# C64_KernalSw_8k.net
KiCad netlist of a schematic drawn in EAGLE
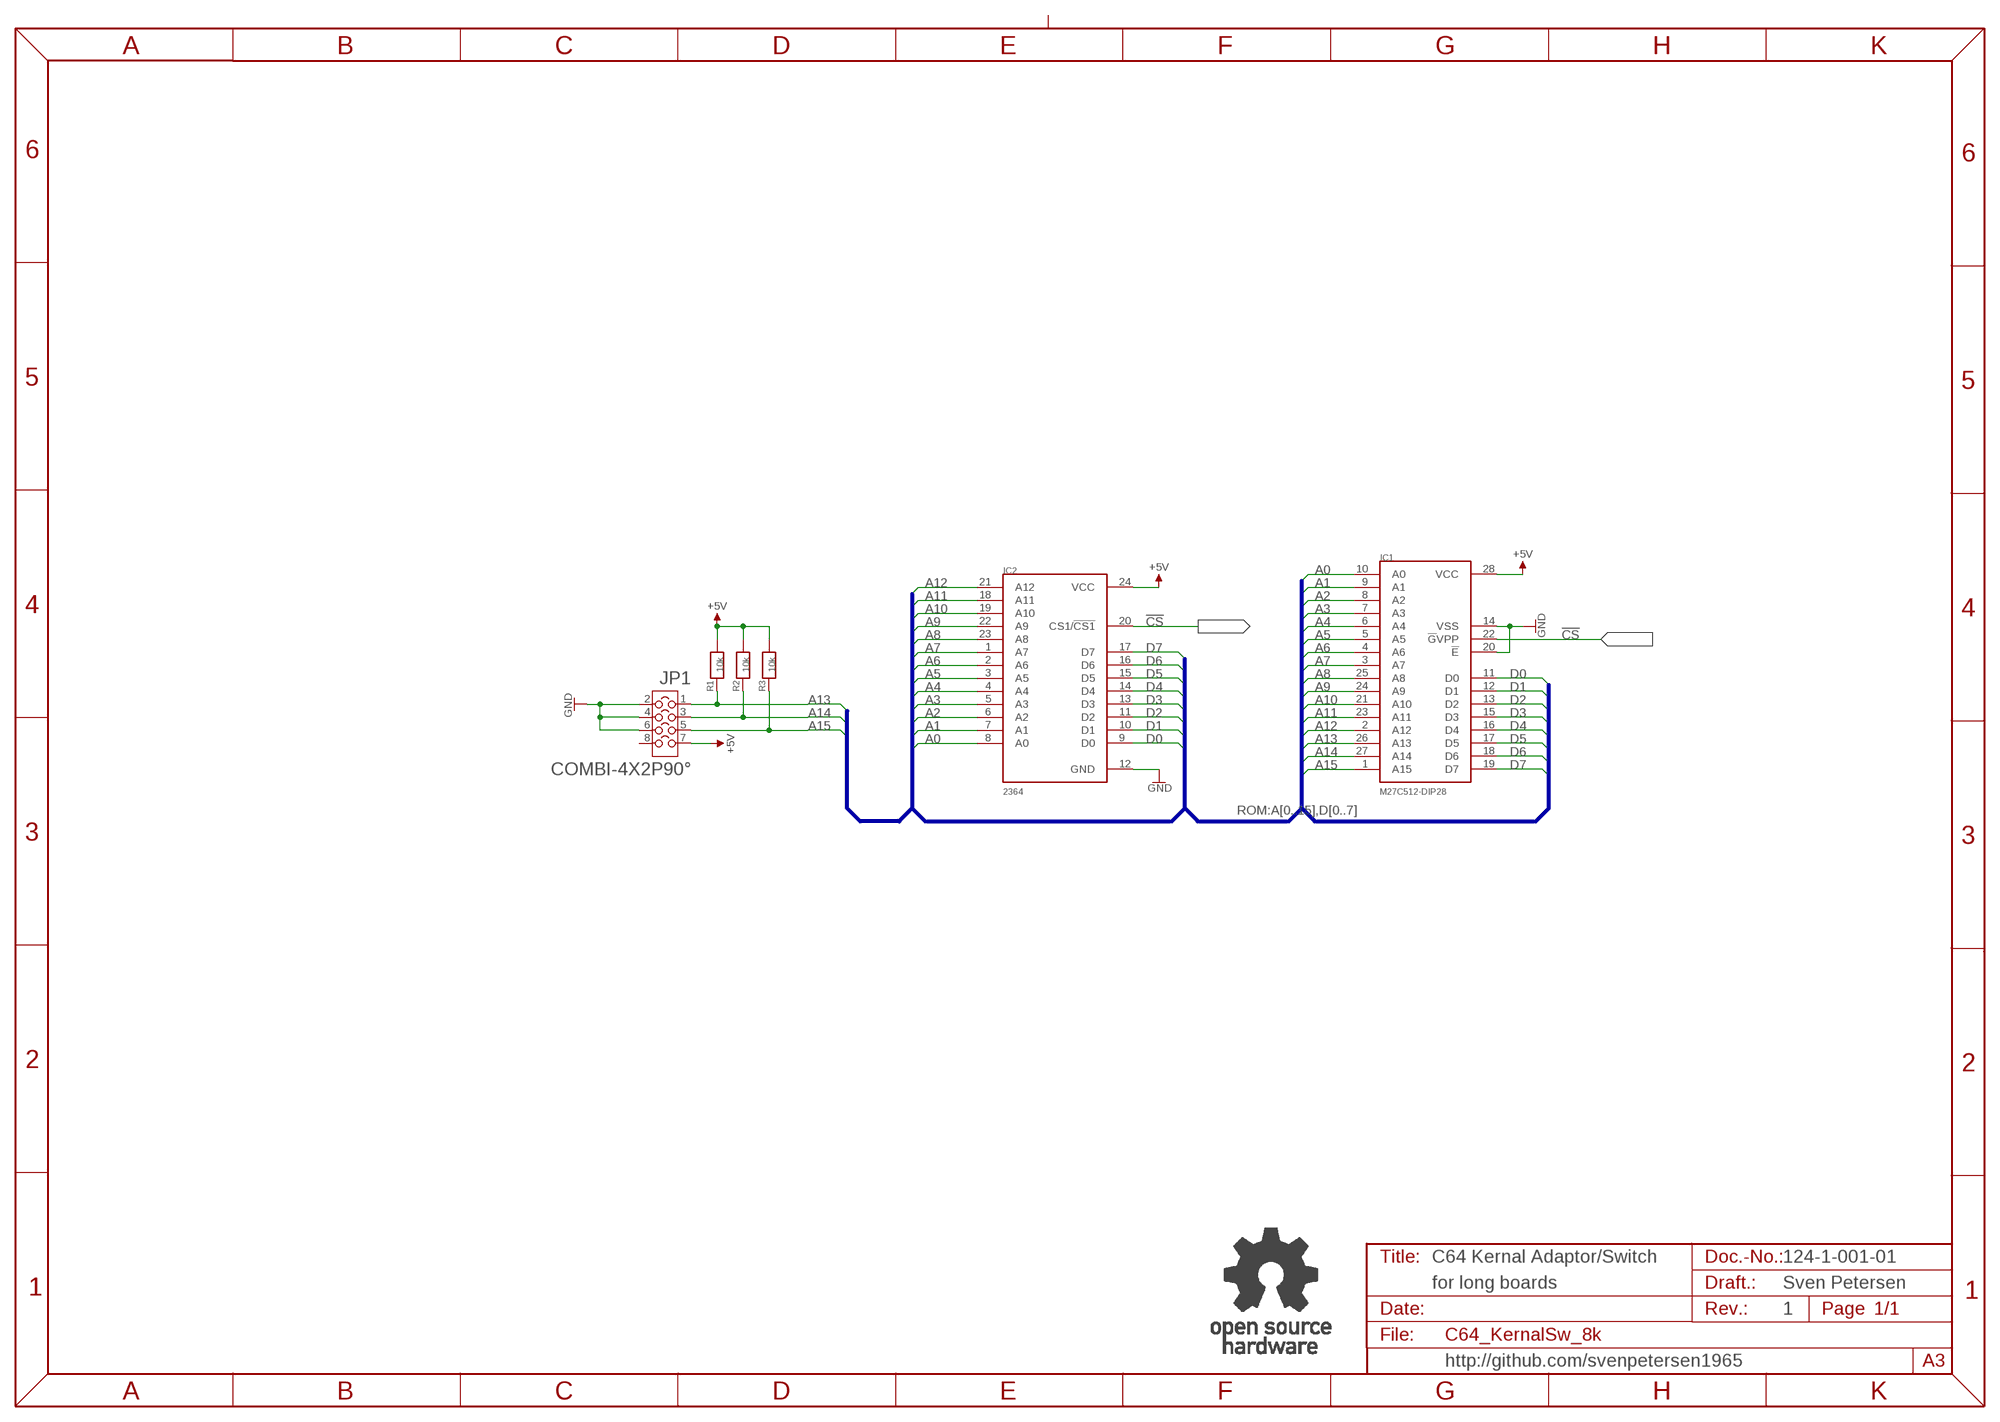
[diagram p0: schematic, sheet 1]

(export (version "E")
  (design (tool "Eeschema 10.0.6"))
  (components
    (comp (ref "IC1")
      (value "M27C512-DIP28")
      (footprint "eagle-import:DIL28-6")
      (libsource (lib "eagle-import") (part "M27C512-DIP28"))
    )
    (comp (ref "IC2")
      (value "2364")
      (footprint "eagle-import:DIL24_SOCKET")
      (libsource (lib "eagle-import") (part "2364"))
    )
    (comp (ref "JP1")
      (value "COMBI-4X2P90°")
      (footprint "eagle-import:COMBI-4X2-90")
      (libsource (lib "eagle-import") (part "COMBI-4X2P90°"))
    )
    (comp (ref "R1")
      (value "10k")
      (footprint "eagle-import:0805")
      (libsource (lib "eagle-import") (part "R-0805"))
    )
    (comp (ref "R2")
      (value "10k")
      (footprint "eagle-import:0805")
      (libsource (lib "eagle-import") (part "R-0805"))
    )
    (comp (ref "R3")
      (value "10k")
      (footprint "eagle-import:0805")
      (libsource (lib "eagle-import") (part "R-0805"))
    )
    (comp (ref "U$11")
      (value "OPEN_SOURCE_HW")
      (footprint "eagle-import:OPENHW")
      (libsource (lib "eagle-import") (part "OPEN_SOURCE_HW"))
    )
  )
  (nets
    (net (code "1") (name "+5V") (class "Default")
      (node (ref "IC1") (pin "28") (pinfunction "VCC_28") (pintype "power_in"))
      (node (ref "IC2") (pin "24") (pinfunction "VCC_24") (pintype "power_in"))
      (node (ref "JP1") (pin "7") (pinfunction "7_7") (pintype "bidirectional"))
      (node (ref "R1") (pin "2") (pinfunction "2_2") (pintype "passive"))
      (node (ref "R2") (pin "2") (pinfunction "2_2") (pintype "passive"))
      (node (ref "R3") (pin "2") (pinfunction "2_2") (pintype "passive"))
    )
    (net (code "2") (name "/A0") (class "Default")
      (node (ref "IC1") (pin "10") (pinfunction "A0_10") (pintype "input"))
      (node (ref "IC2") (pin "8") (pinfunction "A0_8") (pintype "input"))
    )
    (net (code "3") (name "/A1") (class "Default")
      (node (ref "IC1") (pin "9") (pinfunction "A1_9") (pintype "input"))
      (node (ref "IC2") (pin "7") (pinfunction "A1_7") (pintype "input"))
    )
    (net (code "4") (name "/A2") (class "Default")
      (node (ref "IC1") (pin "8") (pinfunction "A2_8") (pintype "input"))
      (node (ref "IC2") (pin "6") (pinfunction "A2_6") (pintype "input"))
    )
    (net (code "5") (name "/A3") (class "Default")
      (node (ref "IC1") (pin "7") (pinfunction "A3_7") (pintype "input"))
      (node (ref "IC2") (pin "5") (pinfunction "A3_5") (pintype "input"))
    )
    (net (code "6") (name "/A4") (class "Default")
      (node (ref "IC1") (pin "6") (pinfunction "A4_6") (pintype "input"))
      (node (ref "IC2") (pin "4") (pinfunction "A4_4") (pintype "input"))
    )
    (net (code "7") (name "/A5") (class "Default")
      (node (ref "IC1") (pin "5") (pinfunction "A5_5") (pintype "input"))
      (node (ref "IC2") (pin "3") (pinfunction "A5_3") (pintype "input"))
    )
    (net (code "8") (name "/A6") (class "Default")
      (node (ref "IC1") (pin "4") (pinfunction "A6_4") (pintype "input"))
      (node (ref "IC2") (pin "2") (pinfunction "A6_2") (pintype "input"))
    )
    (net (code "9") (name "/A7") (class "Default")
      (node (ref "IC1") (pin "3") (pinfunction "A7_3") (pintype "input"))
      (node (ref "IC2") (pin "1") (pinfunction "A7_1") (pintype "input"))
    )
    (net (code "10") (name "/A8") (class "Default")
      (node (ref "IC1") (pin "25") (pinfunction "A8_25") (pintype "input"))
      (node (ref "IC2") (pin "23") (pinfunction "A8_23") (pintype "input"))
    )
    (net (code "11") (name "/A9") (class "Default")
      (node (ref "IC1") (pin "24") (pinfunction "A9_24") (pintype "input"))
      (node (ref "IC2") (pin "22") (pinfunction "A9_22") (pintype "input"))
    )
    (net (code "12") (name "/A10") (class "Default")
      (node (ref "IC1") (pin "21") (pinfunction "A10_21") (pintype "input"))
      (node (ref "IC2") (pin "19") (pinfunction "A10_19") (pintype "input"))
    )
    (net (code "13") (name "/A11") (class "Default")
      (node (ref "IC1") (pin "23") (pinfunction "A11_23") (pintype "input"))
      (node (ref "IC2") (pin "18") (pinfunction "A11_18") (pintype "input"))
    )
    (net (code "14") (name "/A12") (class "Default")
      (node (ref "IC1") (pin "2") (pinfunction "A12_2") (pintype "input"))
      (node (ref "IC2") (pin "21") (pinfunction "A12_21") (pintype "input"))
    )
    (net (code "15") (name "/A13") (class "Default")
      (node (ref "IC1") (pin "26") (pinfunction "A13_26") (pintype "input"))
      (node (ref "JP1") (pin "1") (pinfunction "1_1") (pintype "bidirectional"))
      (node (ref "R1") (pin "1") (pinfunction "1_1") (pintype "passive"))
    )
    (net (code "16") (name "/A14") (class "Default")
      (node (ref "IC1") (pin "27") (pinfunction "A14_27") (pintype "input"))
      (node (ref "JP1") (pin "3") (pinfunction "3_3") (pintype "bidirectional"))
      (node (ref "R2") (pin "1") (pinfunction "1_1") (pintype "passive"))
    )
    (net (code "17") (name "/A15") (class "Default")
      (node (ref "IC1") (pin "1") (pinfunction "A15_1") (pintype "input"))
      (node (ref "JP1") (pin "5") (pinfunction "5_5") (pintype "bidirectional"))
      (node (ref "R3") (pin "1") (pinfunction "1_1") (pintype "passive"))
    )
    (net (code "18") (name "/D0") (class "Default")
      (node (ref "IC1") (pin "11") (pinfunction "D0_11") (pintype "bidirectional"))
      (node (ref "IC2") (pin "9") (pinfunction "D0_9") (pintype "tri_state"))
    )
    (net (code "19") (name "/D1") (class "Default")
      (node (ref "IC1") (pin "12") (pinfunction "D1_12") (pintype "bidirectional"))
      (node (ref "IC2") (pin "10") (pinfunction "D1_10") (pintype "tri_state"))
    )
    (net (code "20") (name "/D2") (class "Default")
      (node (ref "IC1") (pin "13") (pinfunction "D2_13") (pintype "bidirectional"))
      (node (ref "IC2") (pin "11") (pinfunction "D2_11") (pintype "tri_state"))
    )
    (net (code "21") (name "/D3") (class "Default")
      (node (ref "IC1") (pin "15") (pinfunction "D3_15") (pintype "bidirectional"))
      (node (ref "IC2") (pin "13") (pinfunction "D3_13") (pintype "tri_state"))
    )
    (net (code "22") (name "/D4") (class "Default")
      (node (ref "IC1") (pin "16") (pinfunction "D4_16") (pintype "bidirectional"))
      (node (ref "IC2") (pin "14") (pinfunction "D4_14") (pintype "tri_state"))
    )
    (net (code "23") (name "/D5") (class "Default")
      (node (ref "IC1") (pin "17") (pinfunction "D5_17") (pintype "bidirectional"))
      (node (ref "IC2") (pin "15") (pinfunction "D5_15") (pintype "tri_state"))
    )
    (net (code "24") (name "/D6") (class "Default")
      (node (ref "IC1") (pin "18") (pinfunction "D6_18") (pintype "bidirectional"))
      (node (ref "IC2") (pin "16") (pinfunction "D6_16") (pintype "tri_state"))
    )
    (net (code "25") (name "/D7") (class "Default")
      (node (ref "IC1") (pin "19") (pinfunction "D7_19") (pintype "bidirectional"))
      (node (ref "IC2") (pin "17") (pinfunction "D7_17") (pintype "tri_state"))
    )
    (net (code "27") (name "/~{CS}") (class "Default")
      (node (ref "IC1") (pin "22") (pinfunction "~{G}VPP_22") (pintype "input"))
      (node (ref "IC2") (pin "20") (pinfunction "CS1/~{CS1}_20") (pintype "input"))
    )
    (net (code "28") (name "GND") (class "Default")
      (node (ref "IC1") (pin "14") (pinfunction "VSS_14") (pintype "power_in"))
      (node (ref "IC1") (pin "20") (pinfunction "~{E}_20") (pintype "input"))
      (node (ref "IC2") (pin "12") (pinfunction "GND_12") (pintype "power_in"))
      (node (ref "JP1") (pin "2") (pinfunction "2_2") (pintype "bidirectional"))
      (node (ref "JP1") (pin "4") (pinfunction "4_4") (pintype "bidirectional"))
      (node (ref "JP1") (pin "6") (pinfunction "6_6") (pintype "bidirectional"))
    )
    (net (code "29") (name "unconnected-(JP1-Pad8)") (class "Default")
      (node (ref "JP1") (pin "8") (pinfunction "8_8") (pintype "bidirectional"))
    )
  )
)
